# UPS_controller.net
KiCad netlist of a schematic drawn in Altium Designer
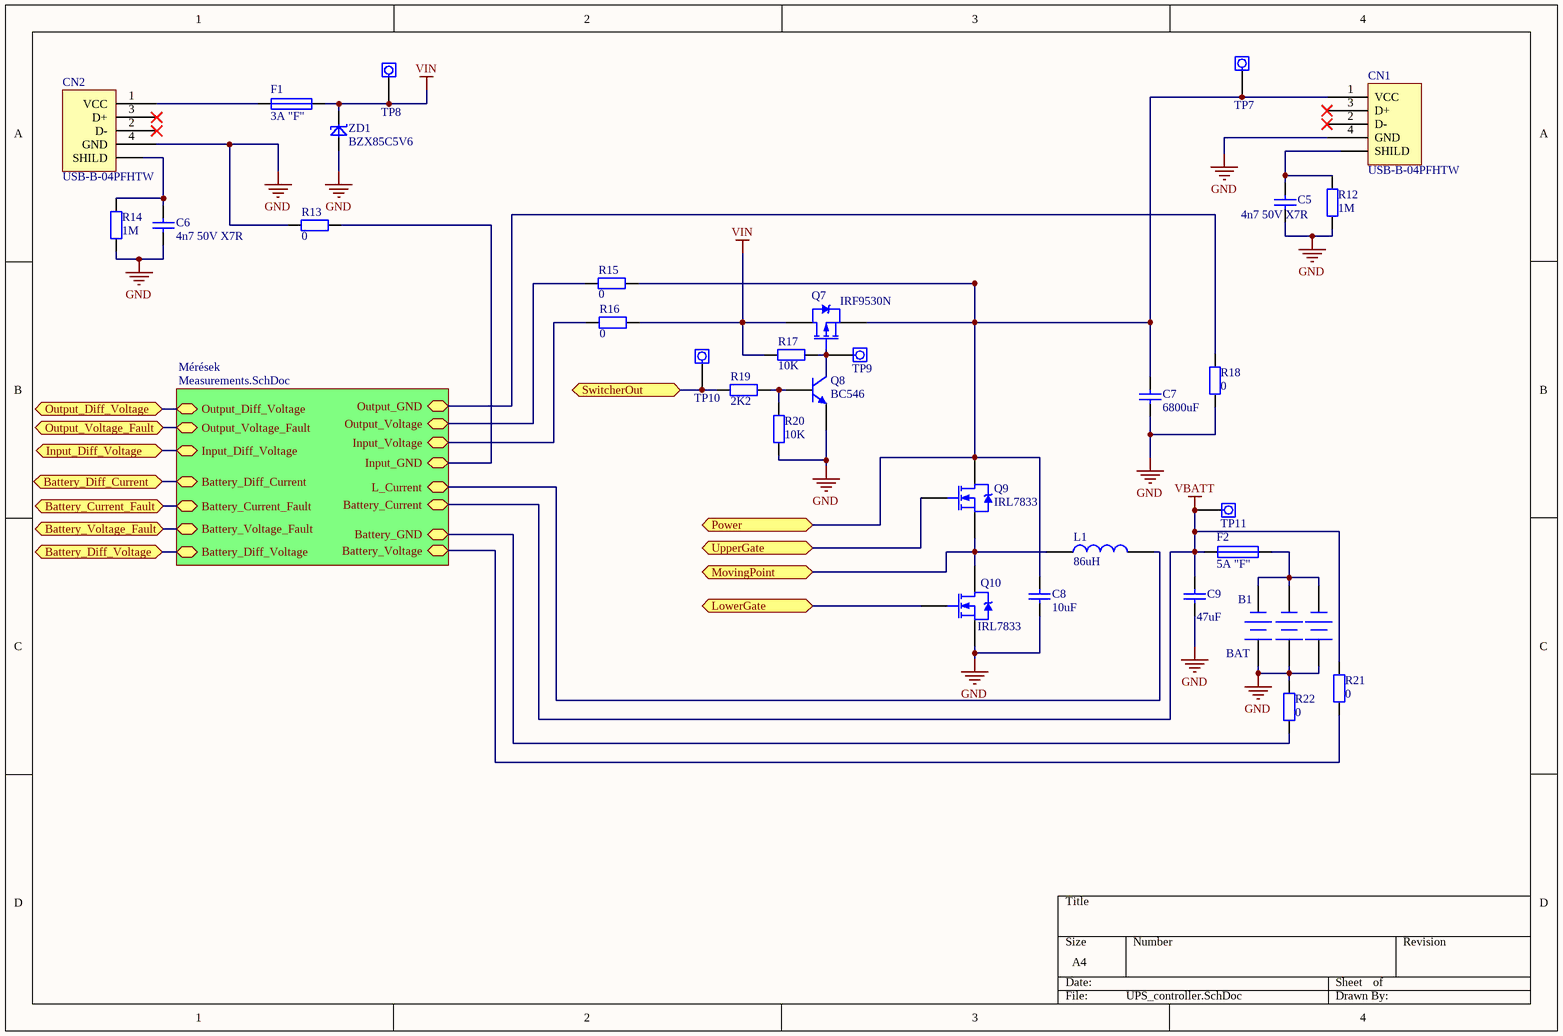
[diagram p0: UPS_controller.SchDoc]

(export (version "E")
  (design (tool "Eeschema 10.0.6"))
  (components
    (comp (ref "B1") (value "BAT") (footprint "Elemtarto_3rekesz") (libsource (lib "hallglib") (part "BAT")))
    (comp (ref "C5")
      (value "4n7 50V X7R")
      (footprint "0805_C")
      (description "SMD kondenzátorok")
      (libsource (lib "MERES") (part "Capacitor_SMD"))
    )
    (comp (ref "C6")
      (value "4n7 50V X7R")
      (footprint "0805_C")
      (description "SMD kondenzátorok")
      (libsource (lib "MERES") (part "Capacitor_SMD"))
    )
    (comp (ref "C7")
      (value "6800uF")
      (footprint "ELKO RM10.16 d=2")
      (description "Capacitor")
      (fields (field (name "VOLTAGE") "16V") (field (name "Comment") "5600uF"))
      (libsource (lib "hallglib") (part "CAP"))
    )
    (comp (ref "C8")
      (value "10uF")
      (footprint "FP_0805_CAP_085")
      (description "Capacitor")
      (fields (field (name "VOLTAGE") "6.3V"))
      (libsource (lib "hallglib") (part "CAP"))
    )
    (comp (ref "C9")
      (value "47uF")
      (footprint "FP_1206_CAP_125")
      (description "Capacitor")
      (fields (field (name "VOLTAGE") "6V3"))
      (libsource (lib "hallglib") (part "CAP"))
    )
    (comp (ref "CN1") (value "USB-B-04PFHTW") (footprint "USB-B") (libsource (lib "MERES") (part "USB-B")))
    (comp (ref "CN2") (value "USB-B-04PFHTW") (footprint "USB-B") (libsource (lib "") (part "USB-B_1")))
    (comp (ref "F1")
      (value "3A \"F\"")
      (footprint "BIZTOSITO_5X20")
      (description "Fuse")
      (libsource (lib "MERES") (part "Fuse"))
    )
    (comp (ref "F2")
      (value "5A \"F\"")
      (footprint "BIZTOSITO_5X20")
      (description "Fuse")
      (libsource (lib "MERES") (part "Fuse"))
    )
    (comp (ref "L1")
      (value "86uH")
      (footprint "toroid")
      (description "Inductor")
      (libsource (lib "hallglib") (part "IND"))
    )
    (comp (ref "Q7")
      (value "IRF9530N")
      (footprint "TO-220-AB")
      (description "P-MOSFET")
      (libsource (lib "hallglib") (part "IRF9530N"))
    )
    (comp (ref "Q8")
      (value "BC546")
      (footprint "TO-92")
      (description "NPN tranzisztor")
      (libsource (lib "hallglib") (part "BC546"))
    )
    (comp (ref "Q9")
      (value "IRL7833")
      (footprint "TO-220-AB")
      (description "N-FET")
      (libsource (lib "hallglib") (part "IRL7833"))
    )
    (comp (ref "Q10")
      (value "IRL7833")
      (footprint "TO-220-AB")
      (description "N-FET")
      (libsource (lib "hallglib") (part "IRL7833"))
    )
    (comp (ref "R12")
      (value "1M")
      (footprint "FP_0805_RES")
      (description "Resistor")
      (libsource (lib "") (part "RES_1"))
    )
    (comp (ref "R13")
      (value "0")
      (footprint "FP_0805_0ohm")
      (description "Resistor")
      (libsource (lib "") (part "RES_1"))
    )
    (comp (ref "R14")
      (value "1M")
      (footprint "FP_0805_RES")
      (description "Resistor")
      (libsource (lib "") (part "RES_2"))
    )
    (comp (ref "R15")
      (value "0")
      (footprint "FP_0805_0ohm")
      (description "Resistor")
      (libsource (lib "") (part "RES_1"))
    )
    (comp (ref "R16")
      (value "0")
      (footprint "FP_0805_0ohm")
      (description "Resistor")
      (libsource (lib "") (part "RES_1"))
    )
    (comp (ref "R17")
      (value "10K")
      (footprint "AXIAL-0.3")
      (description "Resistor")
      (libsource (lib "") (part "RES_3"))
    )
    (comp (ref "R18")
      (value "0")
      (footprint "FP_0805_0ohm")
      (description "Resistor")
      (libsource (lib "") (part "RES_2"))
    )
    (comp (ref "R19")
      (value "2K2")
      (footprint "AXIAL-0.3")
      (description "Resistor")
      (libsource (lib "") (part "RES_1"))
    )
    (comp (ref "R20")
      (value "10K")
      (footprint "AXIAL-0.3")
      (description "Resistor")
      (libsource (lib "") (part "RES_2"))
    )
    (comp (ref "R21")
      (value "0")
      (footprint "FP_0805_0ohm")
      (description "Resistor")
      (libsource (lib "hallglib") (part "RES"))
    )
    (comp (ref "R22")
      (value "0")
      (footprint "FP_0805_0ohm")
      (description "Resistor")
      (libsource (lib "hallglib") (part "RES"))
    )
    (comp (ref "TP7")
      (value "Testpoint")
      (footprint "TESTPOINT_1.5")
      (libsource (lib "MERES") (part "Testpoint"))
    )
    (comp (ref "TP8")
      (value "Testpoint")
      (footprint "TESTPOINT_1.5")
      (libsource (lib "MERES") (part "Testpoint"))
    )
    (comp (ref "TP9")
      (value "Testpoint")
      (footprint "TESTPOINT_1.5")
      (libsource (lib "MERES") (part "Testpoint"))
    )
    (comp (ref "TP10")
      (value "Testpoint")
      (footprint "TESTPOINT_1.5")
      (libsource (lib "MERES") (part "Testpoint"))
    )
    (comp (ref "TP11")
      (value "Testpoint")
      (footprint "TESTPOINT_1.5")
      (libsource (lib "MERES") (part "Testpoint"))
    )
    (comp (ref "ZD1")
      (value "BZX85C5V6")
      (footprint "DO-41-400")
      (description "Zener Diode 5V6 1.3W DO-41")
      (libsource (lib "MERES") (part "BZX85C5V6"))
    )
  )
  (nets
    (net (code "4") (name "/Battery_GND") (class "Default")
      (node (ref "R22") (pin "2") (pinfunction "2_2") (pintype "passive"))
    )
    (net (code "5") (name "/Battery_Voltage") (class "Default")
      (node (ref "R21") (pin "2") (pinfunction "2_2") (pintype "passive"))
    )
    (net (code "8") (name "/Input_GND") (class "Default")
      (node (ref "R13") (pin "2") (pinfunction "2_2") (pintype "passive"))
    )
    (net (code "9") (name "/Input_Voltage") (class "Default")
      (node (ref "R16") (pin "1") (pinfunction "1_1") (pintype "passive"))
    )
    (net (code "10") (name "/L_Current") (class "Default")
      (node (ref "L1") (pin "2") (pinfunction "2_2") (pintype "passive"))
    )
    (net (code "11") (name "/LowerGate") (class "Default")
      (node (ref "Q10") (pin "1") (pinfunction "G_1") (pintype "passive"))
    )
    (net (code "12") (name "/MovingPoint") (class "Default")
      (node (ref "L1") (pin "1") (pinfunction "1_1") (pintype "passive"))
      (node (ref "Q10") (pin "2") (pinfunction "D_2") (pintype "passive"))
      (node (ref "Q9") (pin "3") (pinfunction "S_3") (pintype "passive"))
    )
    (net (code "14") (name "/Output_GND") (class "Default")
      (node (ref "R18") (pin "2") (pinfunction "2_2") (pintype "passive"))
    )
    (net (code "15") (name "/Output_Voltage") (class "Default")
      (node (ref "R15") (pin "1") (pinfunction "1_1") (pintype "passive"))
    )
    (net (code "17") (name "/Power") (class "Default")
      (node (ref "C7") (pin "1") (pinfunction "1_1") (pintype "passive"))
      (node (ref "C8") (pin "2") (pinfunction "2_2") (pintype "passive"))
      (node (ref "CN1") (pin "1") (pinfunction "VCC_1") (pintype "passive"))
      (node (ref "Q7") (pin "3") (pinfunction "S_3") (pintype "passive"))
      (node (ref "Q9") (pin "2") (pinfunction "D_2") (pintype "passive"))
      (node (ref "R15") (pin "2") (pinfunction "2_2") (pintype "passive"))
      (node (ref "TP7") (pin "1") (pinfunction "1_1") (pintype "passive"))
    )
    (net (code "18") (name "/SwitcherOut") (class "Default")
      (node (ref "R19") (pin "1") (pinfunction "1_1") (pintype "passive"))
      (node (ref "TP10") (pin "1") (pinfunction "1_1") (pintype "passive"))
    )
    (net (code "19") (name "/UpperGate") (class "Default")
      (node (ref "Q9") (pin "1") (pinfunction "G_1") (pintype "passive"))
    )
    (net (code "20") (name "GND") (class "Default")
      (node (ref "B1") (pin "1") (pinfunction "GND_1") (pintype "passive"))
      (node (ref "B1") (pin "2") (pinfunction "GND_2") (pintype "passive"))
      (node (ref "B1") (pin "3") (pinfunction "GND_3") (pintype "passive"))
      (node (ref "C5") (pin "2") (pinfunction "2_2") (pintype "passive"))
      (node (ref "C6") (pin "2") (pinfunction "2_2") (pintype "passive"))
      (node (ref "C7") (pin "2") (pinfunction "2_2") (pintype "passive"))
      (node (ref "C8") (pin "1") (pinfunction "1_1") (pintype "passive"))
      (node (ref "C9") (pin "1") (pinfunction "1_1") (pintype "passive"))
      (node (ref "CN1") (pin "4") (pinfunction "GND_4") (pintype "passive"))
      (node (ref "CN2") (pin "4") (pinfunction "GND_4") (pintype "passive"))
      (node (ref "Q10") (pin "3") (pinfunction "S_3") (pintype "passive"))
      (node (ref "Q8") (pin "3") (pinfunction "E_3") (pintype "passive"))
      (node (ref "R12") (pin "1") (pinfunction "1_1") (pintype "passive"))
      (node (ref "R13") (pin "1") (pinfunction "1_1") (pintype "passive"))
      (node (ref "R14") (pin "1") (pinfunction "1_1") (pintype "passive"))
      (node (ref "R18") (pin "1") (pinfunction "1_1") (pintype "passive"))
      (node (ref "R20") (pin "1") (pinfunction "1_1") (pintype "passive"))
      (node (ref "R22") (pin "1") (pinfunction "1_1") (pintype "passive"))
      (node (ref "ZD1") (pin "1") (pinfunction "A_1") (pintype "passive"))
    )
    (net (code "21") (name "Net-(B1-VCC-Pad4)") (class "Default")
      (node (ref "B1") (pin "4") (pinfunction "VCC_4") (pintype "passive"))
      (node (ref "B1") (pin "5") (pinfunction "VCC_5") (pintype "passive"))
      (node (ref "B1") (pin "6") (pinfunction "VCC_6") (pintype "passive"))
      (node (ref "F2") (pin "1") (pinfunction "1_1") (pintype "passive"))
    )
    (net (code "22") (name "Net-(CN1-SHILD)") (class "Default")
      (node (ref "C5") (pin "1") (pinfunction "1_1") (pintype "passive"))
      (node (ref "CN1") (pin "0") (pinfunction "SHILD_0") (pintype "passive"))
      (node (ref "R12") (pin "2") (pinfunction "2_2") (pintype "passive"))
    )
    (net (code "23") (name "Net-(CN2-SHILD)") (class "Default")
      (node (ref "C6") (pin "1") (pinfunction "1_1") (pintype "passive"))
      (node (ref "CN2") (pin "0") (pinfunction "SHILD_0") (pintype "passive"))
      (node (ref "R14") (pin "2") (pinfunction "2_2") (pintype "passive"))
    )
    (net (code "24") (name "Net-(CN2-VCC)") (class "Default")
      (node (ref "CN2") (pin "1") (pinfunction "VCC_1") (pintype "passive"))
      (node (ref "F1") (pin "2") (pinfunction "2_2") (pintype "passive"))
    )
    (net (code "25") (name "Net-(Q7-G)") (class "Default")
      (node (ref "Q7") (pin "1") (pinfunction "G_1") (pintype "passive"))
      (node (ref "Q8") (pin "1") (pinfunction "C_1") (pintype "passive"))
      (node (ref "R17") (pin "1") (pinfunction "1_1") (pintype "passive"))
      (node (ref "TP9") (pin "1") (pinfunction "1_1") (pintype "passive"))
    )
    (net (code "26") (name "Net-(Q8-B)") (class "Default")
      (node (ref "Q8") (pin "2") (pinfunction "B_2") (pintype "passive"))
      (node (ref "R19") (pin "2") (pinfunction "2_2") (pintype "passive"))
      (node (ref "R20") (pin "2") (pinfunction "2_2") (pintype "passive"))
    )
    (net (code "27") (name "VBATT") (class "Default")
      (node (ref "C9") (pin "2") (pinfunction "2_2") (pintype "passive"))
      (node (ref "F2") (pin "2") (pinfunction "2_2") (pintype "passive"))
      (node (ref "R21") (pin "1") (pinfunction "1_1") (pintype "passive"))
      (node (ref "TP11") (pin "1") (pinfunction "1_1") (pintype "passive"))
    )
    (net (code "28") (name "VIN") (class "Default")
      (node (ref "F1") (pin "1") (pinfunction "1_1") (pintype "passive"))
      (node (ref "Q7") (pin "2") (pinfunction "D_2") (pintype "passive"))
      (node (ref "R16") (pin "2") (pinfunction "2_2") (pintype "passive"))
      (node (ref "R17") (pin "2") (pinfunction "2_2") (pintype "passive"))
      (node (ref "TP8") (pin "1") (pinfunction "1_1") (pintype "passive"))
      (node (ref "ZD1") (pin "2") (pinfunction "K_2") (pintype "passive"))
    )
    (net (code "29") (name "unconnected-(CN1-D+-Pad3)") (class "Default")
      (node (ref "CN1") (pin "3") (pinfunction "D+_3") (pintype "passive+no_connect"))
    )
    (net (code "30") (name "unconnected-(CN1-D--Pad2)") (class "Default")
      (node (ref "CN1") (pin "2") (pinfunction "D-_2") (pintype "passive+no_connect"))
    )
    (net (code "31") (name "unconnected-(CN2-D+-Pad3)") (class "Default")
      (node (ref "CN2") (pin "3") (pinfunction "D+_3") (pintype "passive+no_connect"))
    )
    (net (code "32") (name "unconnected-(CN2-D--Pad2)") (class "Default")
      (node (ref "CN2") (pin "2") (pinfunction "D-_2") (pintype "passive+no_connect"))
    )
  )
)
